# Gonies.net
KiCad netlist of a schematic drawn in EAGLE
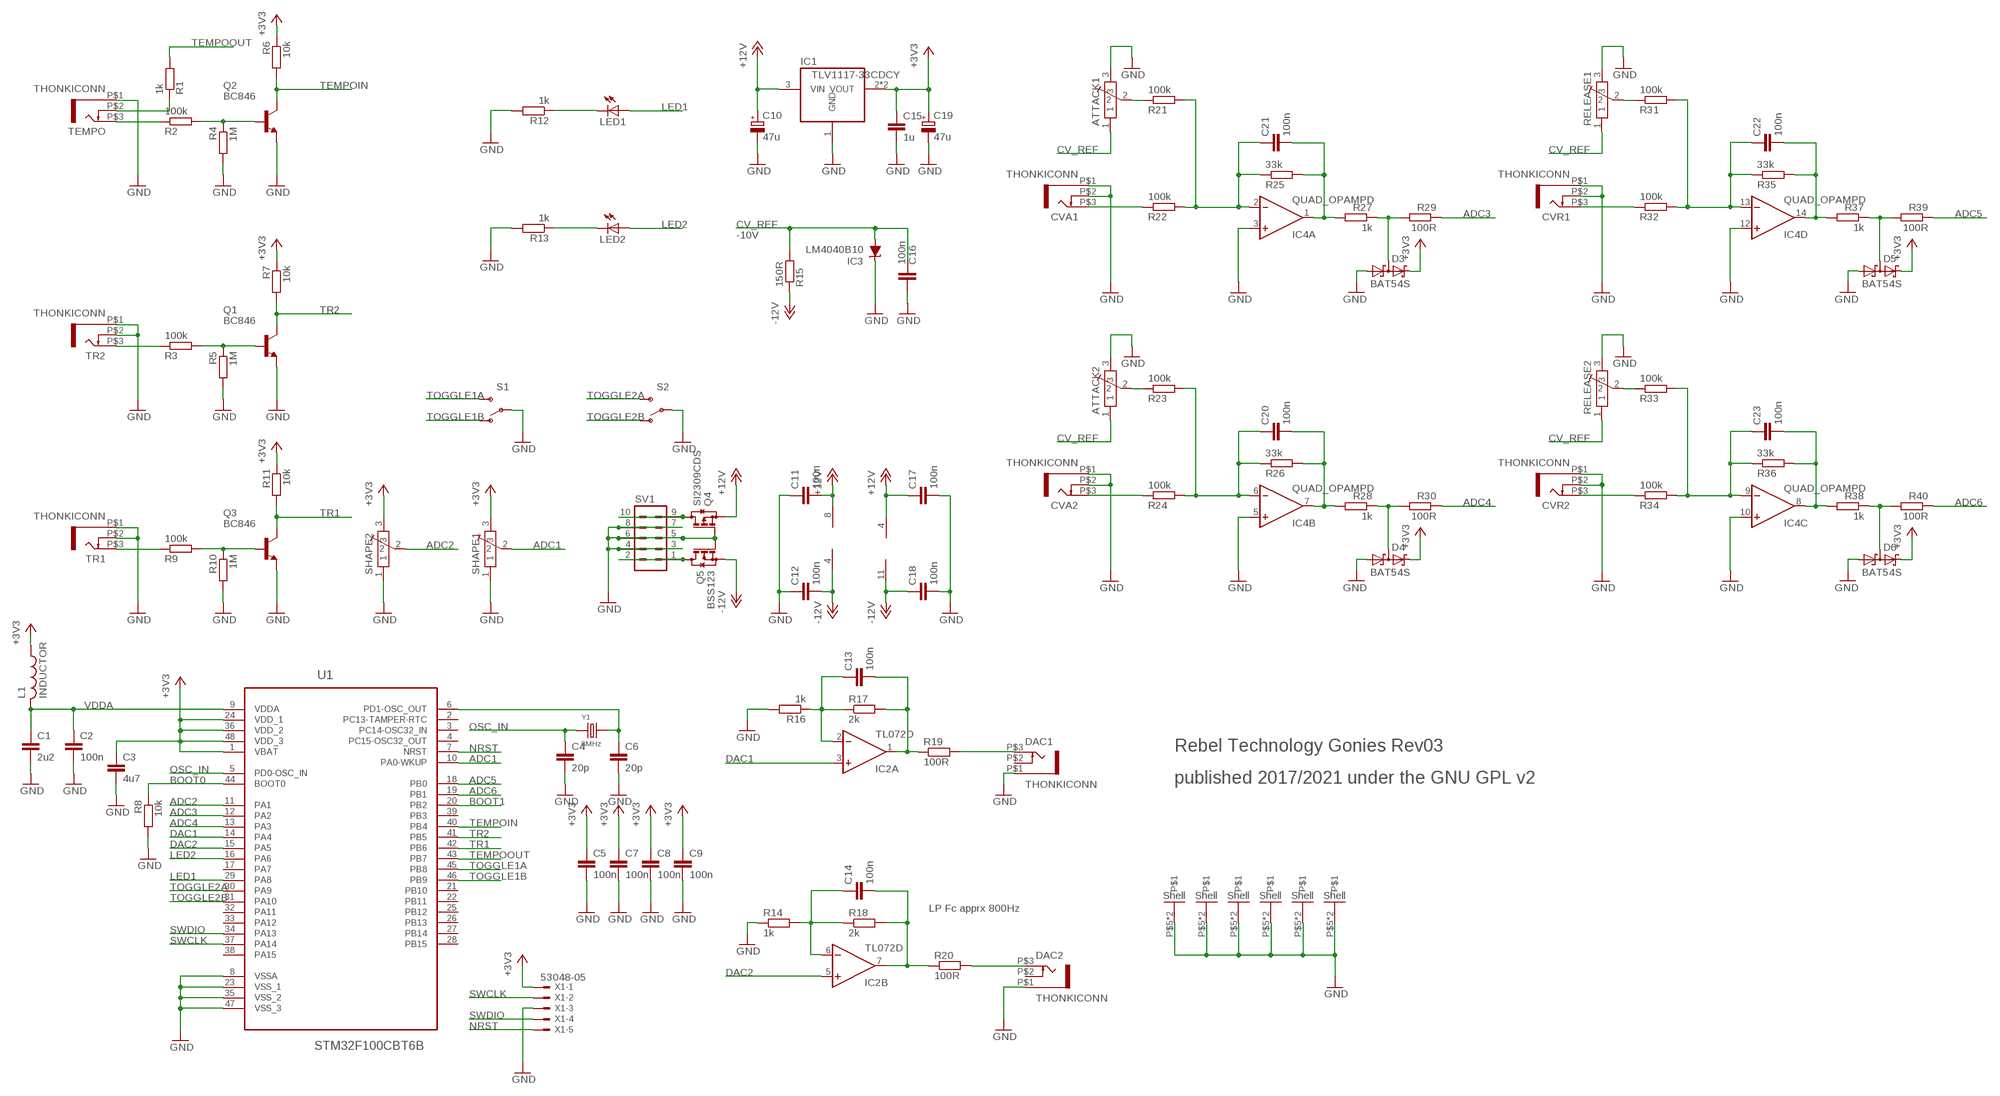
[diagram p0: schematic, sheet 1]

(export (version "E")
  (design (tool "Eeschema 10.0.6"))
  (components
    (comp (ref "ATTACK1")
      (value "POT-ALPS-RK09L1140")
      (footprint "eagle-import:POT-ALPS-RK09L1140")
      (libsource (lib "eagle-import") (part "POT-ALPS-RK09L1140"))
    )
    (comp (ref "ATTACK2")
      (value "POT-ALPS-RK09L1140")
      (footprint "eagle-import:POT-ALPS-RK09L1140")
      (libsource (lib "eagle-import") (part "POT-ALPS-RK09L1140"))
    )
    (comp (ref "C1")
      (value "2u2")
      (footprint "eagle-import:C0603")
      (libsource (lib "eagle-import") (part "C-EUC0603"))
    )
    (comp (ref "C2")
      (value "100n")
      (footprint "eagle-import:C0603")
      (libsource (lib "eagle-import") (part "C-EUC0603"))
    )
    (comp (ref "C3")
      (value "4u7")
      (footprint "eagle-import:C0603")
      (libsource (lib "eagle-import") (part "C-EUC0603"))
    )
    (comp (ref "C4")
      (value "20p")
      (footprint "eagle-import:C0603")
      (libsource (lib "eagle-import") (part "C-EUC0603"))
    )
    (comp (ref "C5")
      (value "100n")
      (footprint "eagle-import:C0603")
      (libsource (lib "eagle-import") (part "C-EUC0603"))
    )
    (comp (ref "C6")
      (value "20p")
      (footprint "eagle-import:C0603")
      (libsource (lib "eagle-import") (part "C-EUC0603"))
    )
    (comp (ref "C7")
      (value "100n")
      (footprint "eagle-import:C0603")
      (libsource (lib "eagle-import") (part "C-EUC0603"))
    )
    (comp (ref "C8")
      (value "100n")
      (footprint "eagle-import:C0603")
      (libsource (lib "eagle-import") (part "C-EUC0603"))
    )
    (comp (ref "C9")
      (value "100n")
      (footprint "eagle-import:C0603")
      (libsource (lib "eagle-import") (part "C-EUC0603"))
    )
    (comp (ref "C10")
      (value "47u")
      (footprint "eagle-import:CPOL-5")
      (libsource (lib "eagle-import") (part "CPOL-EU153CLV-0505"))
    )
    (comp (ref "C11")
      (value "100n")
      (footprint "eagle-import:C0603")
      (libsource (lib "eagle-import") (part "C-EUC0603"))
    )
    (comp (ref "C12")
      (value "100n")
      (footprint "eagle-import:C0603")
      (libsource (lib "eagle-import") (part "C-EUC0603"))
    )
    (comp (ref "C13")
      (value "100n")
      (footprint "eagle-import:C0603")
      (libsource (lib "eagle-import") (part "C-EUC0603"))
    )
    (comp (ref "C14")
      (value "100n")
      (footprint "eagle-import:C0603")
      (libsource (lib "eagle-import") (part "C-EUC0603"))
    )
    (comp (ref "C15")
      (value "1u")
      (footprint "eagle-import:C0603")
      (libsource (lib "eagle-import") (part "C-EUC0603"))
    )
    (comp (ref "C16")
      (value "100n")
      (footprint "eagle-import:C0603")
      (libsource (lib "eagle-import") (part "C-EUC0603"))
    )
    (comp (ref "C17")
      (value "100n")
      (footprint "eagle-import:C0603")
      (libsource (lib "eagle-import") (part "C-EUC0603"))
    )
    (comp (ref "C18")
      (value "100n")
      (footprint "eagle-import:C0603")
      (libsource (lib "eagle-import") (part "C-EUC0603"))
    )
    (comp (ref "C19")
      (value "47u")
      (footprint "eagle-import:CPOL-5")
      (libsource (lib "eagle-import") (part "CPOL-EU153CLV-0505"))
    )
    (comp (ref "C20")
      (value "100n")
      (footprint "eagle-import:C0603")
      (libsource (lib "eagle-import") (part "C-EUC0603"))
    )
    (comp (ref "C21")
      (value "100n")
      (footprint "eagle-import:C0603")
      (libsource (lib "eagle-import") (part "C-EUC0603"))
    )
    (comp (ref "C22")
      (value "100n")
      (footprint "eagle-import:C0603")
      (libsource (lib "eagle-import") (part "C-EUC0603"))
    )
    (comp (ref "C23")
      (value "100n")
      (footprint "eagle-import:C0603")
      (libsource (lib "eagle-import") (part "C-EUC0603"))
    )
    (comp (ref "CVA1")
      (value "THONKICONN")
      (footprint "eagle-import:THONKICONN")
      (libsource (lib "eagle-import") (part "THONKICONN"))
    )
    (comp (ref "CVA2")
      (value "THONKICONN")
      (footprint "eagle-import:THONKICONN")
      (libsource (lib "eagle-import") (part "THONKICONN"))
    )
    (comp (ref "CVR1")
      (value "THONKICONN")
      (footprint "eagle-import:THONKICONN")
      (libsource (lib "eagle-import") (part "THONKICONN"))
    )
    (comp (ref "CVR2")
      (value "THONKICONN")
      (footprint "eagle-import:THONKICONN")
      (libsource (lib "eagle-import") (part "THONKICONN"))
    )
    (comp (ref "D3")
      (value "BAT54S")
      (footprint "eagle-import:SOT23")
      (libsource (lib "eagle-import") (part "BAT54S"))
    )
    (comp (ref "D4")
      (value "BAT54S")
      (footprint "eagle-import:SOT23")
      (libsource (lib "eagle-import") (part "BAT54S"))
    )
    (comp (ref "D5")
      (value "BAT54S")
      (footprint "eagle-import:SOT23")
      (libsource (lib "eagle-import") (part "BAT54S"))
    )
    (comp (ref "D6")
      (value "BAT54S")
      (footprint "eagle-import:SOT23")
      (libsource (lib "eagle-import") (part "BAT54S"))
    )
    (comp (ref "DAC1")
      (value "THONKICONN")
      (footprint "eagle-import:THONKICONN")
      (libsource (lib "eagle-import") (part "THONKICONN"))
    )
    (comp (ref "DAC2")
      (value "THONKICONN")
      (footprint "eagle-import:THONKICONN")
      (libsource (lib "eagle-import") (part "THONKICONN"))
    )
    (comp (ref "IC1")
      (value "TLV1117-33CDCY")
      (footprint "eagle-import:SOT223")
      (fields (field (name "MPN") "REG1117"))
      (libsource (lib "eagle-import") (part "REG1117"))
    )
    (comp (ref "IC2")
      (value "TL072D")
      (footprint "eagle-import:SO08")
      (libsource (lib "eagle-import") (part "TL072D"))
    )
    (comp (ref "IC3")
      (value "LM4040B10")
      (footprint "eagle-import:DBZ_R-PDSO-G3")
      (fields (field (name "MF") "TEXAS INSTRUMENT CONNECTORS") (field (name "MPN") "LM4041C12QDBZT"))
      (libsource (lib "eagle-import") (part "LM4041DBZC12"))
    )
    (comp (ref "IC4")
      (value "QUAD_OPAMPD")
      (footprint "eagle-import:SO14")
      (libsource (lib "eagle-import") (part "QUAD_OPAMPD"))
    )
    (comp (ref "L1")
      (value "INDUCTOR")
      (footprint "eagle-import:0603")
      (libsource (lib "eagle-import") (part "INDUCTOR"))
    )
    (comp (ref "LED1")
      (value "LED3MM")
      (footprint "eagle-import:LED3MM")
      (libsource (lib "eagle-import") (part "LED3MM"))
    )
    (comp (ref "LED2")
      (value "LED3MM")
      (footprint "eagle-import:LED3MM")
      (libsource (lib "eagle-import") (part "LED3MM"))
    )
    (comp (ref "Q1")
      (value "BC846")
      (footprint "eagle-import:SOT23")
      (libsource (lib "eagle-import") (part "BC846"))
    )
    (comp (ref "Q2")
      (value "BC846")
      (footprint "eagle-import:SOT23")
      (libsource (lib "eagle-import") (part "BC846"))
    )
    (comp (ref "Q3")
      (value "BC846")
      (footprint "eagle-import:SOT23")
      (libsource (lib "eagle-import") (part "BC846"))
    )
    (comp (ref "Q4")
      (value "SI2309CDS")
      (footprint "eagle-import:SOT23")
      (libsource (lib "eagle-import") (part "BSS84"))
    )
    (comp (ref "Q5")
      (value "BSS123")
      (footprint "eagle-import:SOT23")
      (libsource (lib "eagle-import") (part "BSS123"))
    )
    (comp (ref "R1")
      (value "1k")
      (footprint "eagle-import:0603")
      (libsource (lib "eagle-import") (part "R-EU_0603"))
    )
    (comp (ref "R2")
      (value "100k")
      (footprint "eagle-import:0603")
      (libsource (lib "eagle-import") (part "R-EU_0603"))
    )
    (comp (ref "R3")
      (value "100k")
      (footprint "eagle-import:0603")
      (libsource (lib "eagle-import") (part "R-EU_0603"))
    )
    (comp (ref "R4")
      (value "1M")
      (footprint "eagle-import:0603")
      (libsource (lib "eagle-import") (part "R-EU_0603"))
    )
    (comp (ref "R5")
      (value "1M")
      (footprint "eagle-import:0603")
      (libsource (lib "eagle-import") (part "R-EU_0603"))
    )
    (comp (ref "R6")
      (value "10k")
      (footprint "eagle-import:0603")
      (libsource (lib "eagle-import") (part "R-EU_0603"))
    )
    (comp (ref "R7")
      (value "10k")
      (footprint "eagle-import:0603")
      (libsource (lib "eagle-import") (part "R-EU_0603"))
    )
    (comp (ref "R8")
      (value "10k")
      (footprint "eagle-import:0603")
      (libsource (lib "eagle-import") (part "R-EU_0603"))
    )
    (comp (ref "R9")
      (value "100k")
      (footprint "eagle-import:0603")
      (libsource (lib "eagle-import") (part "R-EU_0603"))
    )
    (comp (ref "R10")
      (value "1M")
      (footprint "eagle-import:0603")
      (libsource (lib "eagle-import") (part "R-EU_0603"))
    )
    (comp (ref "R11")
      (value "10k")
      (footprint "eagle-import:0603")
      (libsource (lib "eagle-import") (part "R-EU_0603"))
    )
    (comp (ref "R12")
      (value "1k")
      (footprint "eagle-import:0603")
      (libsource (lib "eagle-import") (part "R-EU_0603"))
    )
    (comp (ref "R13")
      (value "1k")
      (footprint "eagle-import:0603")
      (libsource (lib "eagle-import") (part "R-EU_0603"))
    )
    (comp (ref "R14")
      (value "1k")
      (footprint "eagle-import:0603")
      (libsource (lib "eagle-import") (part "R-EU_0603"))
    )
    (comp (ref "R15")
      (value "150R")
      (footprint "eagle-import:0603")
      (libsource (lib "eagle-import") (part "R-EU_0603"))
    )
    (comp (ref "R16")
      (value "1k")
      (footprint "eagle-import:0603")
      (libsource (lib "eagle-import") (part "R-EU_0603"))
    )
    (comp (ref "R17")
      (value "2k")
      (footprint "eagle-import:0603")
      (libsource (lib "eagle-import") (part "R-EU_0603"))
    )
    (comp (ref "R18")
      (value "2k")
      (footprint "eagle-import:0603")
      (libsource (lib "eagle-import") (part "R-EU_0603"))
    )
    (comp (ref "R19")
      (value "100R")
      (footprint "eagle-import:0603")
      (libsource (lib "eagle-import") (part "R-EU_0603"))
    )
    (comp (ref "R20")
      (value "100R")
      (footprint "eagle-import:0603")
      (libsource (lib "eagle-import") (part "R-EU_0603"))
    )
    (comp (ref "R21")
      (value "100k")
      (footprint "eagle-import:0603")
      (libsource (lib "eagle-import") (part "R-EU_0603"))
    )
    (comp (ref "R22")
      (value "100k")
      (footprint "eagle-import:0603")
      (libsource (lib "eagle-import") (part "R-EU_0603"))
    )
    (comp (ref "R23")
      (value "100k")
      (footprint "eagle-import:0603")
      (libsource (lib "eagle-import") (part "R-EU_0603"))
    )
    (comp (ref "R24")
      (value "100k")
      (footprint "eagle-import:0603")
      (libsource (lib "eagle-import") (part "R-EU_0603"))
    )
    (comp (ref "R25")
      (value "33k")
      (footprint "eagle-import:0603")
      (libsource (lib "eagle-import") (part "R-EU_0603"))
    )
    (comp (ref "R26")
      (value "33k")
      (footprint "eagle-import:0603")
      (libsource (lib "eagle-import") (part "R-EU_0603"))
    )
    (comp (ref "R27")
      (value "1k")
      (footprint "eagle-import:0603")
      (libsource (lib "eagle-import") (part "R-EU_0603"))
    )
    (comp (ref "R28")
      (value "1k")
      (footprint "eagle-import:0603")
      (libsource (lib "eagle-import") (part "R-EU_0603"))
    )
    (comp (ref "R29")
      (value "100R")
      (footprint "eagle-import:0603")
      (libsource (lib "eagle-import") (part "R-EU_0603"))
    )
    (comp (ref "R30")
      (value "100R")
      (footprint "eagle-import:0603")
      (libsource (lib "eagle-import") (part "R-EU_0603"))
    )
    (comp (ref "R31")
      (value "100k")
      (footprint "eagle-import:0603")
      (libsource (lib "eagle-import") (part "R-EU_0603"))
    )
    (comp (ref "R32")
      (value "100k")
      (footprint "eagle-import:0603")
      (libsource (lib "eagle-import") (part "R-EU_0603"))
    )
    (comp (ref "R33")
      (value "100k")
      (footprint "eagle-import:0603")
      (libsource (lib "eagle-import") (part "R-EU_0603"))
    )
    (comp (ref "R34")
      (value "100k")
      (footprint "eagle-import:0603")
      (libsource (lib "eagle-import") (part "R-EU_0603"))
    )
    (comp (ref "R35")
      (value "33k")
      (footprint "eagle-import:0603")
      (libsource (lib "eagle-import") (part "R-EU_0603"))
    )
    (comp (ref "R36")
      (value "33k")
      (footprint "eagle-import:0603")
      (libsource (lib "eagle-import") (part "R-EU_0603"))
    )
    (comp (ref "R37")
      (value "1k")
      (footprint "eagle-import:0603")
      (libsource (lib "eagle-import") (part "R-EU_0603"))
    )
    (comp (ref "R38")
      (value "1k")
      (footprint "eagle-import:0603")
      (libsource (lib "eagle-import") (part "R-EU_0603"))
    )
    (comp (ref "R39")
      (value "100R")
      (footprint "eagle-import:0603")
      (libsource (lib "eagle-import") (part "R-EU_0603"))
    )
    (comp (ref "R40")
      (value "100R")
      (footprint "eagle-import:0603")
      (libsource (lib "eagle-import") (part "R-EU_0603"))
    )
    (comp (ref "RELEASE1")
      (value "POT-ALPS-RK09L1140")
      (footprint "eagle-import:POT-ALPS-RK09L1140")
      (libsource (lib "eagle-import") (part "POT-ALPS-RK09L1140"))
    )
    (comp (ref "RELEASE2")
      (value "POT-ALPS-RK09L1140")
      (footprint "eagle-import:POT-ALPS-RK09L1140")
      (libsource (lib "eagle-import") (part "POT-ALPS-RK09L1140"))
    )
    (comp (ref "S1")
      (value "SWITCH-SPST")
      (footprint "eagle-import:SWITCH-SPDT-SALECOM-T8014")
      (libsource (lib "eagle-import") (part "SWITCH-SPST"))
    )
    (comp (ref "S2")
      (value "SWITCH-SPST")
      (footprint "eagle-import:SWITCH-SPDT-SALECOM-T8014")
      (libsource (lib "eagle-import") (part "SWITCH-SPST"))
    )
    (comp (ref "SHAPE1")
      (value "POT-ALPS-RK09L1140")
      (footprint "eagle-import:POT-ALPS-RK09L1140")
      (libsource (lib "eagle-import") (part "POT-ALPS-RK09L1140"))
    )
    (comp (ref "SHAPE2")
      (value "POT-ALPS-RK09L1140")
      (footprint "eagle-import:POT-ALPS-RK09L1140")
      (libsource (lib "eagle-import") (part "POT-ALPS-RK09L1140"))
    )
    (comp (ref "SV1")
      (value "MA05-2")
      (footprint "eagle-import:MA05-2")
      (libsource (lib "eagle-import") (part "MA05-2"))
    )
    (comp (ref "TEMPO")
      (value "THONKICONN")
      (footprint "eagle-import:THONKICONN")
      (libsource (lib "eagle-import") (part "THONKICONN"))
    )
    (comp (ref "TR1")
      (value "THONKICONN")
      (footprint "eagle-import:THONKICONN")
      (libsource (lib "eagle-import") (part "THONKICONN"))
    )
    (comp (ref "TR2")
      (value "THONKICONN")
      (footprint "eagle-import:THONKICONN")
      (libsource (lib "eagle-import") (part "THONKICONN"))
    )
    (comp (ref "U1")
      (value "STM32F100CBT6B")
      (footprint "eagle-import:QFP50P900X900X160-48N")
      (libsource (lib "eagle-import") (part "STM32F100CBT6B"))
    )
    (comp (ref "X1")
      (value "53048-05")
      (footprint "eagle-import:53048-05")
      (fields (field (name "MF") "MOLEX") (field (name "MPN") "53048-0510"))
      (libsource (lib "eagle-import") (part "53?-05048"))
    )
    (comp (ref "Y1")
      (value "8MHz")
      (footprint "eagle-import:X2-SMD-5.0X3.2X1.3MM")
      (fields (field (name "MPN") "5032/2P"))
      (libsource (lib "eagle-import") (part "SMD-CRYSTAL-8MHZ-20PF-20PPM(2P-5.0X3.2MM)"))
    )
  )
  (nets
    (net (code "1") (name "+3V3") (class "Default")
      (node (ref "C15") (pin "1") (pinfunction "1_1") (pintype "passive"))
      (node (ref "C19") (pin "+") (pinfunction "+_+") (pintype "passive"))
      (node (ref "C3") (pin "1") (pinfunction "1_1") (pintype "passive"))
      (node (ref "C5") (pin "1") (pinfunction "1_1") (pintype "passive"))
      (node (ref "C7") (pin "1") (pinfunction "1_1") (pintype "passive"))
      (node (ref "C8") (pin "1") (pinfunction "1_1") (pintype "passive"))
      (node (ref "C9") (pin "1") (pinfunction "1_1") (pintype "passive"))
      (node (ref "D3") (pin "2") (pinfunction "C2_2") (pintype "passive"))
      (node (ref "D4") (pin "2") (pinfunction "C2_2") (pintype "passive"))
      (node (ref "D5") (pin "2") (pinfunction "C2_2") (pintype "passive"))
      (node (ref "D6") (pin "2") (pinfunction "C2_2") (pintype "passive"))
      (node (ref "IC1") (pin "2") (pinfunction "VOUT_2") (pintype "output"))
      (node (ref "IC1") (pin "4") (pinfunction "VOUT_4") (pintype "output"))
      (node (ref "L1") (pin "1") (pinfunction "1_1") (pintype "passive"))
      (node (ref "R11") (pin "1") (pinfunction "1_1") (pintype "passive"))
      (node (ref "R6") (pin "1") (pinfunction "1_1") (pintype "passive"))
      (node (ref "R7") (pin "1") (pinfunction "1_1") (pintype "passive"))
      (node (ref "SHAPE1") (pin "3") (pinfunction "3_3") (pintype "bidirectional"))
      (node (ref "SHAPE2") (pin "3") (pinfunction "3_3") (pintype "bidirectional"))
      (node (ref "U1") (pin "1") (pinfunction "VBAT_1") (pintype "power_in"))
      (node (ref "U1") (pin "24") (pinfunction "VDD_1_24") (pintype "power_in"))
      (node (ref "U1") (pin "36") (pinfunction "VDD_2_36") (pintype "power_in"))
      (node (ref "U1") (pin "48") (pinfunction "VDD_3_48") (pintype "power_in"))
      (node (ref "X1") (pin "1") (pinfunction "S_1") (pintype "passive"))
    )
    (net (code "2") (name "+12V") (class "Default")
      (node (ref "C10") (pin "+") (pinfunction "+_+") (pintype "passive"))
      (node (ref "C11") (pin "2") (pinfunction "2_2") (pintype "passive"))
      (node (ref "C17") (pin "1") (pinfunction "1_1") (pintype "passive"))
      (node (ref "IC1") (pin "3") (pinfunction "VIN_3") (pintype "input"))
      (node (ref "IC2") (pin "8") (pinfunction "V+_8") (pintype "power_in"))
      (node (ref "IC4") (pin "4") (pinfunction "V+_4") (pintype "power_in"))
      (node (ref "Q4") (pin "2") (pinfunction "S_2") (pintype "passive"))
    )
    (net (code "3") (name "-12V") (class "Default")
      (node (ref "C12") (pin "2") (pinfunction "2_2") (pintype "passive"))
      (node (ref "C18") (pin "1") (pinfunction "1_1") (pintype "passive"))
      (node (ref "IC2") (pin "4") (pinfunction "V-_4") (pintype "power_in"))
      (node (ref "IC4") (pin "11") (pinfunction "V-_11") (pintype "power_in"))
      (node (ref "Q5") (pin "2") (pinfunction "S_2") (pintype "passive"))
      (node (ref "R15") (pin "1") (pinfunction "1_1") (pintype "passive"))
    )
    (net (code "4") (name "/ADC1") (class "Default")
      (node (ref "SHAPE1") (pin "2") (pinfunction "2_2") (pintype "bidirectional"))
      (node (ref "U1") (pin "10") (pinfunction "PA0-WKUP_10") (pintype "bidirectional"))
    )
    (net (code "5") (name "/ADC2") (class "Default")
      (node (ref "SHAPE2") (pin "2") (pinfunction "2_2") (pintype "bidirectional"))
      (node (ref "U1") (pin "11") (pinfunction "PA1_11") (pintype "bidirectional"))
    )
    (net (code "6") (name "/ADC3") (class "Default")
      (node (ref "R29") (pin "1") (pinfunction "1_1") (pintype "passive"))
      (node (ref "U1") (pin "12") (pinfunction "PA2_12") (pintype "bidirectional"))
    )
    (net (code "7") (name "/ADC4") (class "Default")
      (node (ref "R30") (pin "1") (pinfunction "1_1") (pintype "passive"))
      (node (ref "U1") (pin "13") (pinfunction "PA3_13") (pintype "bidirectional"))
    )
    (net (code "8") (name "/ADC5") (class "Default")
      (node (ref "R39") (pin "1") (pinfunction "1_1") (pintype "passive"))
      (node (ref "U1") (pin "18") (pinfunction "PB0_18") (pintype "bidirectional"))
    )
    (net (code "9") (name "/ADC6") (class "Default")
      (node (ref "R40") (pin "1") (pinfunction "1_1") (pintype "passive"))
      (node (ref "U1") (pin "19") (pinfunction "PB1_19") (pintype "bidirectional"))
    )
    (net (code "10") (name "/BOOT0") (class "Default")
      (node (ref "R8") (pin "1") (pinfunction "1_1") (pintype "passive"))
      (node (ref "U1") (pin "44") (pinfunction "BOOT0_44") (pintype "input"))
    )
    (net (code "11") (name "/BOOT1") (class "Default")
      (node (ref "U1") (pin "20") (pinfunction "PB2_20") (pintype "bidirectional"))
    )
    (net (code "12") (name "/CV_REF") (class "Default")
      (node (ref "ATTACK1") (pin "1") (pinfunction "1_1") (pintype "bidirectional"))
      (node (ref "ATTACK2") (pin "1") (pinfunction "1_1") (pintype "bidirectional"))
      (node (ref "C16") (pin "1") (pinfunction "1_1") (pintype "passive"))
      (node (ref "IC3") (pin "2") (pinfunction "A_2") (pintype "passive"))
      (node (ref "R15") (pin "2") (pinfunction "2_2") (pintype "passive"))
      (node (ref "RELEASE1") (pin "1") (pinfunction "1_1") (pintype "bidirectional"))
      (node (ref "RELEASE2") (pin "1") (pinfunction "1_1") (pintype "bidirectional"))
    )
    (net (code "13") (name "/DAC1") (class "Default")
      (node (ref "IC2") (pin "3") (pinfunction "+IN_3") (pintype "input"))
      (node (ref "U1") (pin "14") (pinfunction "PA4_14") (pintype "bidirectional"))
    )
    (net (code "14") (name "/DAC2") (class "Default")
      (node (ref "IC2") (pin "5") (pinfunction "+IN_5") (pintype "input"))
      (node (ref "U1") (pin "15") (pinfunction "PA5_15") (pintype "bidirectional"))
    )
    (net (code "15") (name "/LED1") (class "Default")
      (node (ref "LED1") (pin "A") (pinfunction "A_A") (pintype "passive"))
      (node (ref "U1") (pin "29") (pinfunction "PA8_29") (pintype "bidirectional"))
    )
    (net (code "16") (name "/LED2") (class "Default")
      (node (ref "LED2") (pin "A") (pinfunction "A_A") (pintype "passive"))
      (node (ref "U1") (pin "16") (pinfunction "PA6_16") (pintype "bidirectional"))
    )
    (net (code "17") (name "/NRST") (class "Default")
      (node (ref "U1") (pin "7") (pinfunction "NRST_7") (pintype "bidirectional"))
      (node (ref "X1") (pin "5") (pinfunction "S_5") (pintype "passive"))
    )
    (net (code "18") (name "/OSC_IN") (class "Default")
      (node (ref "C4") (pin "1") (pinfunction "1_1") (pintype "passive"))
      (node (ref "U1") (pin "5") (pinfunction "PD0-OSC_IN_5") (pintype "input"))
      (node (ref "Y1") (pin "1") (pinfunction "1_1") (pintype "passive"))
    )
    (net (code "19") (name "/SWCLK") (class "Default")
      (node (ref "U1") (pin "37") (pinfunction "PA14_37") (pintype "bidirectional"))
      (node (ref "X1") (pin "2") (pinfunction "S_2") (pintype "passive"))
    )
    (net (code "20") (name "/SWDIO") (class "Default")
      (node (ref "U1") (pin "34") (pinfunction "PA13_34") (pintype "bidirectional"))
      (node (ref "X1") (pin "4") (pinfunction "S_4") (pintype "passive"))
    )
    (net (code "21") (name "/TEMPOIN") (class "Default")
      (node (ref "Q2") (pin "3") (pinfunction "C_3") (pintype "passive"))
      (node (ref "R6") (pin "2") (pinfunction "2_2") (pintype "passive"))
      (node (ref "U1") (pin "40") (pinfunction "PB4_40") (pintype "bidirectional"))
    )
    (net (code "22") (name "/TEMPOOUT") (class "Default")
      (node (ref "R1") (pin "2") (pinfunction "2_2") (pintype "passive"))
      (node (ref "U1") (pin "43") (pinfunction "PB7_43") (pintype "bidirectional"))
    )
    (net (code "23") (name "/TOGGLE1A") (class "Default")
      (node (ref "S1") (pin "3") (pinfunction "S_3") (pintype "passive"))
      (node (ref "U1") (pin "45") (pinfunction "PB8_45") (pintype "bidirectional"))
    )
    (net (code "24") (name "/TOGGLE1B") (class "Default")
      (node (ref "S1") (pin "1") (pinfunction "O_1") (pintype "passive"))
      (node (ref "U1") (pin "46") (pinfunction "PB9_46") (pintype "bidirectional"))
    )
    (net (code "25") (name "/TOGGLE2A") (class "Default")
      (node (ref "S2") (pin "3") (pinfunction "S_3") (pintype "passive"))
      (node (ref "U1") (pin "30") (pinfunction "PA9_30") (pintype "bidirectional"))
    )
    (net (code "26") (name "/TOGGLE2B") (class "Default")
      (node (ref "S2") (pin "1") (pinfunction "O_1") (pintype "passive"))
      (node (ref "U1") (pin "31") (pinfunction "PA10_31") (pintype "bidirectional"))
    )
    (net (code "27") (name "/TR1") (class "Default")
      (node (ref "Q3") (pin "3") (pinfunction "C_3") (pintype "passive"))
      (node (ref "R11") (pin "2") (pinfunction "2_2") (pintype "passive"))
      (node (ref "U1") (pin "42") (pinfunction "PB6_42") (pintype "bidirectional"))
    )
    (net (code "28") (name "/TR2") (class "Default")
      (node (ref "Q1") (pin "3") (pinfunction "C_3") (pintype "passive"))
      (node (ref "R7") (pin "2") (pinfunction "2_2") (pintype "passive"))
      (node (ref "U1") (pin "41") (pinfunction "PB5_41") (pintype "bidirectional"))
    )
    (net (code "29") (name "/VDDA") (class "Default")
      (node (ref "C1") (pin "1") (pinfunction "1_1") (pintype "passive"))
      (node (ref "C2") (pin "1") (pinfunction "1_1") (pintype "passive"))
      (node (ref "L1") (pin "2") (pinfunction "2_2") (pintype "passive"))
      (node (ref "U1") (pin "9") (pinfunction "VDDA_9") (pintype "power_in"))
    )
    (net (code "30") (name "GND") (class "Default")
      (node (ref "ATTACK1") (pin "3") (pinfunction "3_3") (pintype "bidirectional"))
      (node (ref "ATTACK1") (pin "P$5") (pinfunction "P$1_P$5") (pintype "bidirectional"))
      (node (ref "ATTACK1") (pin "P$6") (pinfunction "P$1_P$6") (pintype "bidirectional"))
      (node (ref "ATTACK2") (pin "3") (pinfunction "3_3") (pintype "bidirectional"))
      (node (ref "ATTACK2") (pin "P$5") (pinfunction "P$1_P$5") (pintype "bidirectional"))
      (node (ref "ATTACK2") (pin "P$6") (pinfunction "P$1_P$6") (pintype "bidirectional"))
      (node (ref "C1") (pin "2") (pinfunction "2_2") (pintype "passive"))
      (node (ref "C10") (pin "-") (pinfunction "-_-") (pintype "passive"))
      (node (ref "C11") (pin "1") (pinfunction "1_1") (pintype "passive"))
      (node (ref "C12") (pin "1") (pinfunction "1_1") (pintype "passive"))
      (node (ref "C15") (pin "2") (pinfunction "2_2") (pintype "passive"))
      (node (ref "C16") (pin "2") (pinfunction "2_2") (pintype "passive"))
      (node (ref "C17") (pin "2") (pinfunction "2_2") (pintype "passive"))
      (node (ref "C18") (pin "2") (pinfunction "2_2") (pintype "passive"))
      (node (ref "C19") (pin "-") (pinfunction "-_-") (pintype "passive"))
      (node (ref "C2") (pin "2") (pinfunction "2_2") (pintype "passive"))
      (node (ref "C3") (pin "2") (pinfunction "2_2") (pintype "passive"))
      (node (ref "C4") (pin "2") (pinfunction "2_2") (pintype "passive"))
      (node (ref "C5") (pin "2") (pinfunction "2_2") (pintype "passive"))
      (node (ref "C6") (pin "2") (pinfunction "2_2") (pintype "passive"))
      (node (ref "C7") (pin "2") (pinfunction "2_2") (pintype "passive"))
      (node (ref "C8") (pin "2") (pinfunction "2_2") (pintype "passive"))
      (node (ref "C9") (pin "2") (pinfunction "2_2") (pintype "passive"))
      (node (ref "CVA1") (pin "P$1") (pinfunction "5_P$1") (pintype "passive"))
      (node (ref "CVA1") (pin "P$2") (pinfunction "4_P$2") (pintype "passive"))
      (node (ref "CVA2") (pin "P$1") (pinfunction "5_P$1") (pintype "passive"))
      (node (ref "CVA2") (pin "P$2") (pinfunction "4_P$2") (pintype "passive"))
      (node (ref "CVR1") (pin "P$1") (pinfunction "5_P$1") (pintype "passive"))
      (node (ref "CVR1") (pin "P$2") (pinfunction "4_P$2") (pintype "passive"))
      (node (ref "CVR2") (pin "P$1") (pinfunction "5_P$1") (pintype "passive"))
      (node (ref "CVR2") (pin "P$2") (pinfunction "4_P$2") (pintype "passive"))
      (node (ref "D3") (pin "1") (pinfunction "A1_1") (pintype "passive"))
      (node (ref "D4") (pin "1") (pinfunction "A1_1") (pintype "passive"))
      (node (ref "D5") (pin "1") (pinfunction "A1_1") (pintype "passive"))
      (node (ref "D6") (pin "1") (pinfunction "A1_1") (pintype "passive"))
      (node (ref "DAC1") (pin "P$1") (pinfunction "5_P$1") (pintype "passive"))
      (node (ref "DAC2") (pin "P$1") (pinfunction "5_P$1") (pintype "passive"))
      (node (ref "IC1") (pin "1") (pinfunction "GND_1") (pintype "power_in"))
      (node (ref "IC3") (pin "1") (pinfunction "C_1") (pintype "passive"))
      (node (ref "IC4") (pin "10") (pinfunction "+IN_10") (pintype "input"))
      (node (ref "IC4") (pin "12") (pinfunction "+IN_12") (pintype "input"))
      (node (ref "IC4") (pin "3") (pinfunction "+IN_3") (pintype "input"))
      (node (ref "IC4") (pin "5") (pinfunction "+IN_5") (pintype "input"))
      (node (ref "Q1") (pin "2") (pinfunction "E_2") (pintype "passive"))
      (node (ref "Q2") (pin "2") (pinfunction "E_2") (pintype "passive"))
      (node (ref "Q3") (pin "2") (pinfunction "E_2") (pintype "passive"))
      (node (ref "Q4") (pin "1") (pinfunction "G_1") (pintype "passive"))
      (node (ref "Q5") (pin "1") (pinfunction "G_1") (pintype "passive"))
      (node (ref "R10") (pin "2") (pinfunction "2_2") (pintype "passive"))
      (node (ref "R12") (pin "2") (pinfunction "2_2") (pintype "passive"))
      (node (ref "R13") (pin "2") (pinfunction "2_2") (pintype "passive"))
      (node (ref "R14") (pin "1") (pinfunction "1_1") (pintype "passive"))
      (node (ref "R16") (pin "2") (pinfunction "2_2") (pintype "passive"))
      (node (ref "R4") (pin "2") (pinfunction "2_2") (pintype "passive"))
      (node (ref "R5") (pin "2") (pinfunction "2_2") (pintype "passive"))
      (node (ref "R8") (pin "2") (pinfunction "2_2") (pintype "passive"))
      (node (ref "RELEASE1") (pin "3") (pinfunction "3_3") (pintype "bidirectional"))
      (node (ref "RELEASE1") (pin "P$5") (pinfunction "P$1_P$5") (pintype "bidirectional"))
      (node (ref "RELEASE1") (pin "P$6") (pinfunction "P$1_P$6") (pintype "bidirectional"))
      (node (ref "RELEASE2") (pin "3") (pinfunction "3_3") (pintype "bidirectional"))
      (node (ref "RELEASE2") (pin "P$5") (pinfunction "P$1_P$5") (pintype "bidirectional"))
      (node (ref "RELEASE2") (pin "P$6") (pinfunction "P$1_P$6") (pintype "bidirectional"))
      (node (ref "S1") (pin "2") (pinfunction "P_2") (pintype "passive"))
      (node (ref "S2") (pin "2") (pinfunction "P_2") (pintype "passive"))
      (node (ref "SHAPE1") (pin "1") (pinfunction "1_1") (pintype "bidirectional"))
      (node (ref "SHAPE1") (pin "P$5") (pinfunction "P$1_P$5") (pintype "bidirectional"))
      (node (ref "SHAPE1") (pin "P$6") (pinfunction "P$1_P$6") (pintype "bidirectional"))
      (node (ref "SHAPE2") (pin "1") (pinfunction "1_1") (pintype "bidirectional"))
      (node (ref "SHAPE2") (pin "P$5") (pinfunction "P$1_P$5") (pintype "bidirectional"))
      (node (ref "SHAPE2") (pin "P$6") (pinfunction "P$1_P$6") (pintype "bidirectional"))
      (node (ref "SV1") (pin "3") (pinfunction "3_3") (pintype "passive"))
      (node (ref "SV1") (pin "4") (pinfunction "4_4") (pintype "passive"))
      (node (ref "SV1") (pin "5") (pinfunction "5_5") (pintype "passive"))
      (node (ref "SV1") (pin "6") (pinfunction "6_6") (pintype "passive"))
      (node (ref "SV1") (pin "7") (pinfunction "7_7") (pintype "passive"))
      (node (ref "SV1") (pin "8") (pinfunction "8_8") (pintype "passive"))
      (node (ref "TEMPO") (pin "P$1") (pinfunction "5_P$1") (pintype "passive"))
      (node (ref "TR1") (pin "P$1") (pinfunction "5_P$1") (pintype "passive"))
      (node (ref "TR1") (pin "P$2") (pinfunction "4_P$2") (pintype "passive"))
      (node (ref "TR2") (pin "P$1") (pinfunction "5_P$1") (pintype "passive"))
      (node (ref "TR2") (pin "P$2") (pinfunction "4_P$2") (pintype "passive"))
      (node (ref "U1") (pin "23") (pinfunction "VSS_1_23") (pintype "power_in"))
      (node (ref "U1") (pin "35") (pinfunction "VSS_2_35") (pintype "power_in"))
      (node (ref "U1") (pin "47") (pinfunction "VSS_3_47") (pintype "power_in"))
      (node (ref "U1") (pin "8") (pinfunction "VSSA_8") (pintype "power_in"))
      (node (ref "X1") (pin "3") (pinfunction "S_3") (pintype "passive"))
    )
    (net (code "31") (name "Net-(ATTACK1-Pad2)") (class "Default")
      (node (ref "ATTACK1") (pin "2") (pinfunction "2_2") (pintype "bidirectional"))
      (node (ref "R21") (pin "1") (pinfunction "1_1") (pintype "passive"))
    )
    (net (code "32") (name "Net-(ATTACK2-Pad2)") (class "Default")
      (node (ref "ATTACK2") (pin "2") (pinfunction "2_2") (pintype "bidirectional"))
      (node (ref "R23") (pin "1") (pinfunction "1_1") (pintype "passive"))
    )
    (net (code "33") (name "Net-(CVA1-3)") (class "Default")
      (node (ref "CVA1") (pin "P$3") (pinfunction "3_P$3") (pintype "passive"))
      (node (ref "R22") (pin "1") (pinfunction "1_1") (pintype "passive"))
    )
    (net (code "34") (name "Net-(CVA2-3)") (class "Default")
      (node (ref "CVA2") (pin "P$3") (pinfunction "3_P$3") (pintype "passive"))
      (node (ref "R24") (pin "1") (pinfunction "1_1") (pintype "passive"))
    )
    (net (code "35") (name "Net-(CVR1-3)") (class "Default")
      (node (ref "CVR1") (pin "P$3") (pinfunction "3_P$3") (pintype "passive"))
      (node (ref "R32") (pin "1") (pinfunction "1_1") (pintype "passive"))
    )
    (net (code "36") (name "Net-(CVR2-3)") (class "Default")
      (node (ref "CVR2") (pin "P$3") (pinfunction "3_P$3") (pintype "passive"))
      (node (ref "R34") (pin "1") (pinfunction "1_1") (pintype "passive"))
    )
    (net (code "37") (name "Net-(D3-C1A2)") (class "Default")
      (node (ref "D3") (pin "3") (pinfunction "C1A2_3") (pintype "passive"))
      (node (ref "R27") (pin "1") (pinfunction "1_1") (pintype "passive"))
      (node (ref "R29") (pin "2") (pinfunction "2_2") (pintype "passive"))
    )
    (net (code "38") (name "Net-(D4-C1A2)") (class "Default")
      (node (ref "D4") (pin "3") (pinfunction "C1A2_3") (pintype "passive"))
      (node (ref "R28") (pin "1") (pinfunction "1_1") (pintype "passive"))
      (node (ref "R30") (pin "2") (pinfunction "2_2") (pintype "passive"))
    )
    (net (code "39") (name "Net-(D5-C1A2)") (class "Default")
      (node (ref "D5") (pin "3") (pinfunction "C1A2_3") (pintype "passive"))
      (node (ref "R37") (pin "1") (pinfunction "1_1") (pintype "passive"))
      (node (ref "R39") (pin "2") (pinfunction "2_2") (pintype "passive"))
    )
    (net (code "40") (name "Net-(D6-C1A2)") (class "Default")
      (node (ref "D6") (pin "3") (pinfunction "C1A2_3") (pintype "passive"))
      (node (ref "R38") (pin "1") (pinfunction "1_1") (pintype "passive"))
      (node (ref "R40") (pin "2") (pinfunction "2_2") (pintype "passive"))
    )
    (net (code "41") (name "Net-(DAC1-3)") (class "Default")
      (node (ref "DAC1") (pin "P$3") (pinfunction "3_P$3") (pintype "passive"))
      (node (ref "R19") (pin "2") (pinfunction "2_2") (pintype "passive"))
    )
    (net (code "42") (name "Net-(DAC2-3)") (class "Default")
      (node (ref "DAC2") (pin "P$3") (pinfunction "3_P$3") (pintype "passive"))
      (node (ref "R20") (pin "2") (pinfunction "2_2") (pintype "passive"))
    )
    (net (code "43") (name "Net-(IC2A--IN)") (class "Default")
      (node (ref "C13") (pin "1") (pinfunction "1_1") (pintype "passive"))
      (node (ref "IC2") (pin "2") (pinfunction "-IN_2") (pintype "input"))
      (node (ref "R16") (pin "1") (pinfunction "1_1") (pintype "passive"))
      (node (ref "R17") (pin "1") (pinfunction "1_1") (pintype "passive"))
    )
    (net (code "44") (name "Net-(IC2A-OUT)") (class "Default")
      (node (ref "C13") (pin "2") (pinfunction "2_2") (pintype "passive"))
      (node (ref "IC2") (pin "1") (pinfunction "OUT_1") (pintype "output"))
      (node (ref "R17") (pin "2") (pinfunction "2_2") (pintype "passive"))
      (node (ref "R19") (pin "1") (pinfunction "1_1") (pintype "passive"))
    )
    (net (code "45") (name "Net-(IC2B--IN)") (class "Default")
      (node (ref "C14") (pin "1") (pinfunction "1_1") (pintype "passive"))
      (node (ref "IC2") (pin "6") (pinfunction "-IN_6") (pintype "input"))
      (node (ref "R14") (pin "2") (pinfunction "2_2") (pintype "passive"))
      (node (ref "R18") (pin "1") (pinfunction "1_1") (pintype "passive"))
    )
    (net (code "46") (name "Net-(IC2B-OUT)") (class "Default")
      (node (ref "C14") (pin "2") (pinfunction "2_2") (pintype "passive"))
      (node (ref "IC2") (pin "7") (pinfunction "OUT_7") (pintype "output"))
      (node (ref "R18") (pin "2") (pinfunction "2_2") (pintype "passive"))
      (node (ref "R20") (pin "1") (pinfunction "1_1") (pintype "passive"))
    )
    (net (code "47") (name "Net-(IC4A--IN)") (class "Default")
      (node (ref "C21") (pin "1") (pinfunction "1_1") (pintype "passive"))
      (node (ref "IC4") (pin "2") (pinfunction "-IN_2") (pintype "input"))
      (node (ref "R21") (pin "2") (pinfunction "2_2") (pintype "passive"))
      (node (ref "R22") (pin "2") (pinfunction "2_2") (pintype "passive"))
      (node (ref "R25") (pin "1") (pinfunction "1_1") (pintype "passive"))
    )
    (net (code "48") (name "Net-(IC4A-OUT)") (class "Default")
      (node (ref "C21") (pin "2") (pinfunction "2_2") (pintype "passive"))
      (node (ref "IC4") (pin "1") (pinfunction "OUT_1") (pintype "output"))
      (node (ref "R25") (pin "2") (pinfunction "2_2") (pintype "passive"))
      (node (ref "R27") (pin "2") (pinfunction "2_2") (pintype "passive"))
    )
    (net (code "49") (name "Net-(IC4B--IN)") (class "Default")
      (node (ref "C20") (pin "1") (pinfunction "1_1") (pintype "passive"))
      (node (ref "IC4") (pin "6") (pinfunction "-IN_6") (pintype "input"))
      (node (ref "R23") (pin "2") (pinfunction "2_2") (pintype "passive"))
      (node (ref "R24") (pin "2") (pinfunction "2_2") (pintype "passive"))
      (node (ref "R26") (pin "1") (pinfunction "1_1") (pintype "passive"))
    )
    (net (code "50") (name "Net-(IC4B-OUT)") (class "Default")
      (node (ref "C20") (pin "2") (pinfunction "2_2") (pintype "passive"))
      (node (ref "IC4") (pin "7") (pinfunction "OUT_7") (pintype "output"))
      (node (ref "R26") (pin "2") (pinfunction "2_2") (pintype "passive"))
      (node (ref "R28") (pin "2") (pinfunction "2_2") (pintype "passive"))
    )
    (net (code "51") (name "Net-(IC4C--IN)") (class "Default")
      (node (ref "C23") (pin "1") (pinfunction "1_1") (pintype "passive"))
      (node (ref "IC4") (pin "9") (pinfunction "-IN_9") (pintype "input"))
      (node (ref "R33") (pin "2") (pinfunction "2_2") (pintype "passive"))
      (node (ref "R34") (pin "2") (pinfunction "2_2") (pintype "passive"))
      (node (ref "R36") (pin "1") (pinfunction "1_1") (pintype "passive"))
    )
    (net (code "52") (name "Net-(IC4C-OUT)") (class "Default")
      (node (ref "C23") (pin "2") (pinfunction "2_2") (pintype "passive"))
      (node (ref "IC4") (pin "8") (pinfunction "OUT_8") (pintype "output"))
      (node (ref "R36") (pin "2") (pinfunction "2_2") (pintype "passive"))
      (node (ref "R38") (pin "2") (pinfunction "2_2") (pintype "passive"))
    )
    (net (code "53") (name "Net-(IC4D--IN)") (class "Default")
      (node (ref "C22") (pin "1") (pinfunction "1_1") (pintype "passive"))
      (node (ref "IC4") (pin "13") (pinfunction "-IN_13") (pintype "input"))
      (node (ref "R31") (pin "2") (pinfunction "2_2") (pintype "passive"))
      (node (ref "R32") (pin "2") (pinfunction "2_2") (pintype "passive"))
      (node (ref "R35") (pin "1") (pinfunction "1_1") (pintype "passive"))
    )
    (net (code "54") (name "Net-(IC4D-OUT)") (class "Default")
      (node (ref "C22") (pin "2") (pinfunction "2_2") (pintype "passive"))
      (node (ref "IC4") (pin "14") (pinfunction "OUT_14") (pintype "output"))
      (node (ref "R35") (pin "2") (pinfunction "2_2") (pintype "passive"))
      (node (ref "R37") (pin "2") (pinfunction "2_2") (pintype "passive"))
    )
    (net (code "55") (name "Net-(LED1-C)") (class "Default")
      (node (ref "LED1") (pin "K") (pinfunction "C_K") (pintype "passive"))
      (node (ref "R12") (pin "1") (pinfunction "1_1") (pintype "passive"))
    )
    (net (code "56") (name "Net-(LED2-C)") (class "Default")
      (node (ref "LED2") (pin "K") (pinfunction "C_K") (pintype "passive"))
      (node (ref "R13") (pin "1") (pinfunction "1_1") (pintype "passive"))
    )
    (net (code "57") (name "Net-(Q1-B)") (class "Default")
      (node (ref "Q1") (pin "1") (pinfunction "B_1") (pintype "passive"))
      (node (ref "R3") (pin "2") (pinfunction "2_2") (pintype "passive"))
      (node (ref "R5") (pin "1") (pinfunction "1_1") (pintype "passive"))
    )
    (net (code "58") (name "Net-(Q2-B)") (class "Default")
      (node (ref "Q2") (pin "1") (pinfunction "B_1") (pintype "passive"))
      (node (ref "R2") (pin "2") (pinfunction "2_2") (pintype "passive"))
      (node (ref "R4") (pin "1") (pinfunction "1_1") (pintype "passive"))
    )
    (net (code "59") (name "Net-(Q3-B)") (class "Default")
      (node (ref "Q3") (pin "1") (pinfunction "B_1") (pintype "passive"))
      (node (ref "R10") (pin "1") (pinfunction "1_1") (pintype "passive"))
      (node (ref "R9") (pin "2") (pinfunction "2_2") (pintype "passive"))
    )
    (net (code "60") (name "Net-(Q4-D)") (class "Default")
      (node (ref "Q4") (pin "3") (pinfunction "D_3") (pintype "passive"))
      (node (ref "SV1") (pin "10") (pinfunction "10_10") (pintype "passive"))
      (node (ref "SV1") (pin "9") (pinfunction "9_9") (pintype "passive"))
    )
    (net (code "61") (name "Net-(Q5-D)") (class "Default")
      (node (ref "Q5") (pin "3") (pinfunction "D_3") (pintype "passive"))
      (node (ref "SV1") (pin "1") (pinfunction "1_1") (pintype "passive"))
      (node (ref "SV1") (pin "2") (pinfunction "2_2") (pintype "passive"))
    )
    (net (code "62") (name "Net-(R31-Pad1)") (class "Default")
      (node (ref "R31") (pin "1") (pinfunction "1_1") (pintype "passive"))
      (node (ref "RELEASE1") (pin "2") (pinfunction "2_2") (pintype "bidirectional"))
    )
    (net (code "63") (name "Net-(R33-Pad1)") (class "Default")
      (node (ref "R33") (pin "1") (pinfunction "1_1") (pintype "passive"))
      (node (ref "RELEASE2") (pin "2") (pinfunction "2_2") (pintype "bidirectional"))
    )
    (net (code "64") (name "Net-(TEMPO-3)") (class "Default")
      (node (ref "R2") (pin "1") (pinfunction "1_1") (pintype "passive"))
      (node (ref "TEMPO") (pin "P$3") (pinfunction "3_P$3") (pintype "passive"))
    )
    (net (code "65") (name "Net-(TEMPO-4)") (class "Default")
      (node (ref "R1") (pin "1") (pinfunction "1_1") (pintype "passive"))
      (node (ref "TEMPO") (pin "P$2") (pinfunction "4_P$2") (pintype "passive"))
    )
    (net (code "66") (name "Net-(TR1-3)") (class "Default")
      (node (ref "R9") (pin "1") (pinfunction "1_1") (pintype "passive"))
      (node (ref "TR1") (pin "P$3") (pinfunction "3_P$3") (pintype "passive"))
    )
    (net (code "67") (name "Net-(TR2-3)") (class "Default")
      (node (ref "R3") (pin "1") (pinfunction "1_1") (pintype "passive"))
      (node (ref "TR2") (pin "P$3") (pinfunction "3_P$3") (pintype "passive"))
    )
    (net (code "68") (name "Net-(U1-PD1-OSC_OUT)") (class "Default")
      (node (ref "C6") (pin "1") (pinfunction "1_1") (pintype "passive"))
      (node (ref "U1") (pin "6") (pinfunction "PD1-OSC_OUT_6") (pintype "output"))
      (node (ref "Y1") (pin "2") (pinfunction "2_2") (pintype "passive"))
    )
    (net (code "69") (name "unconnected-(DAC1-4-PadP$2)") (class "Default")
      (node (ref "DAC1") (pin "P$2") (pinfunction "4_P$2") (pintype "passive"))
    )
    (net (code "70") (name "unconnected-(DAC2-4-PadP$2)") (class "Default")
      (node (ref "DAC2") (pin "P$2") (pinfunction "4_P$2") (pintype "passive"))
    )
    (net (code "71") (name "unconnected-(U1-PA7-Pad17)") (class "Default")
      (node (ref "U1") (pin "17") (pinfunction "PA7_17") (pintype "bidirectional"))
    )
    (net (code "72") (name "unconnected-(U1-PA11-Pad32)") (class "Default")
      (node (ref "U1") (pin "32") (pinfunction "PA11_32") (pintype "bidirectional"))
    )
    (net (code "73") (name "unconnected-(U1-PA12-Pad33)") (class "Default")
      (node (ref "U1") (pin "33") (pinfunction "PA12_33") (pintype "bidirectional"))
    )
    (net (code "74") (name "unconnected-(U1-PA15-Pad38)") (class "Default")
      (node (ref "U1") (pin "38") (pinfunction "PA15_38") (pintype "bidirectional"))
    )
    (net (code "75") (name "unconnected-(U1-PB3-Pad39)") (class "Default")
      (node (ref "U1") (pin "39") (pinfunction "PB3_39") (pintype "bidirectional"))
    )
    (net (code "76") (name "unconnected-(U1-PB10-Pad21)") (class "Default")
      (node (ref "U1") (pin "21") (pinfunction "PB10_21") (pintype "bidirectional"))
    )
    (net (code "77") (name "unconnected-(U1-PB11-Pad22)") (class "Default")
      (node (ref "U1") (pin "22") (pinfunction "PB11_22") (pintype "bidirectional"))
    )
    (net (code "78") (name "unconnected-(U1-PB12-Pad25)") (class "Default")
      (node (ref "U1") (pin "25") (pinfunction "PB12_25") (pintype "bidirectional"))
    )
    (net (code "79") (name "unconnected-(U1-PB13-Pad26)") (class "Default")
      (node (ref "U1") (pin "26") (pinfunction "PB13_26") (pintype "bidirectional"))
    )
    (net (code "80") (name "unconnected-(U1-PB14-Pad27)") (class "Default")
      (node (ref "U1") (pin "27") (pinfunction "PB14_27") (pintype "bidirectional"))
    )
    (net (code "81") (name "unconnected-(U1-PB15-Pad28)") (class "Default")
      (node (ref "U1") (pin "28") (pinfunction "PB15_28") (pintype "bidirectional"))
    )
    (net (code "82") (name "unconnected-(U1-PC13-TAMPER-RTC-Pad2)") (class "Default")
      (node (ref "U1") (pin "2") (pinfunction "PC13-TAMPER-RTC_2") (pintype "bidirectional"))
    )
    (net (code "83") (name "unconnected-(U1-PC14-OSC32_IN-Pad3)") (class "Default")
      (node (ref "U1") (pin "3") (pinfunction "PC14-OSC32_IN_3") (pintype "bidirectional"))
    )
    (net (code "84") (name "unconnected-(U1-PC15-OSC32_OUT-Pad4)") (class "Default")
      (node (ref "U1") (pin "4") (pinfunction "PC15-OSC32_OUT_4") (pintype "bidirectional"))
    )
  )
)
